# PWMDriver.net
KiCad netlist of a schematic drawn in Altium Designer
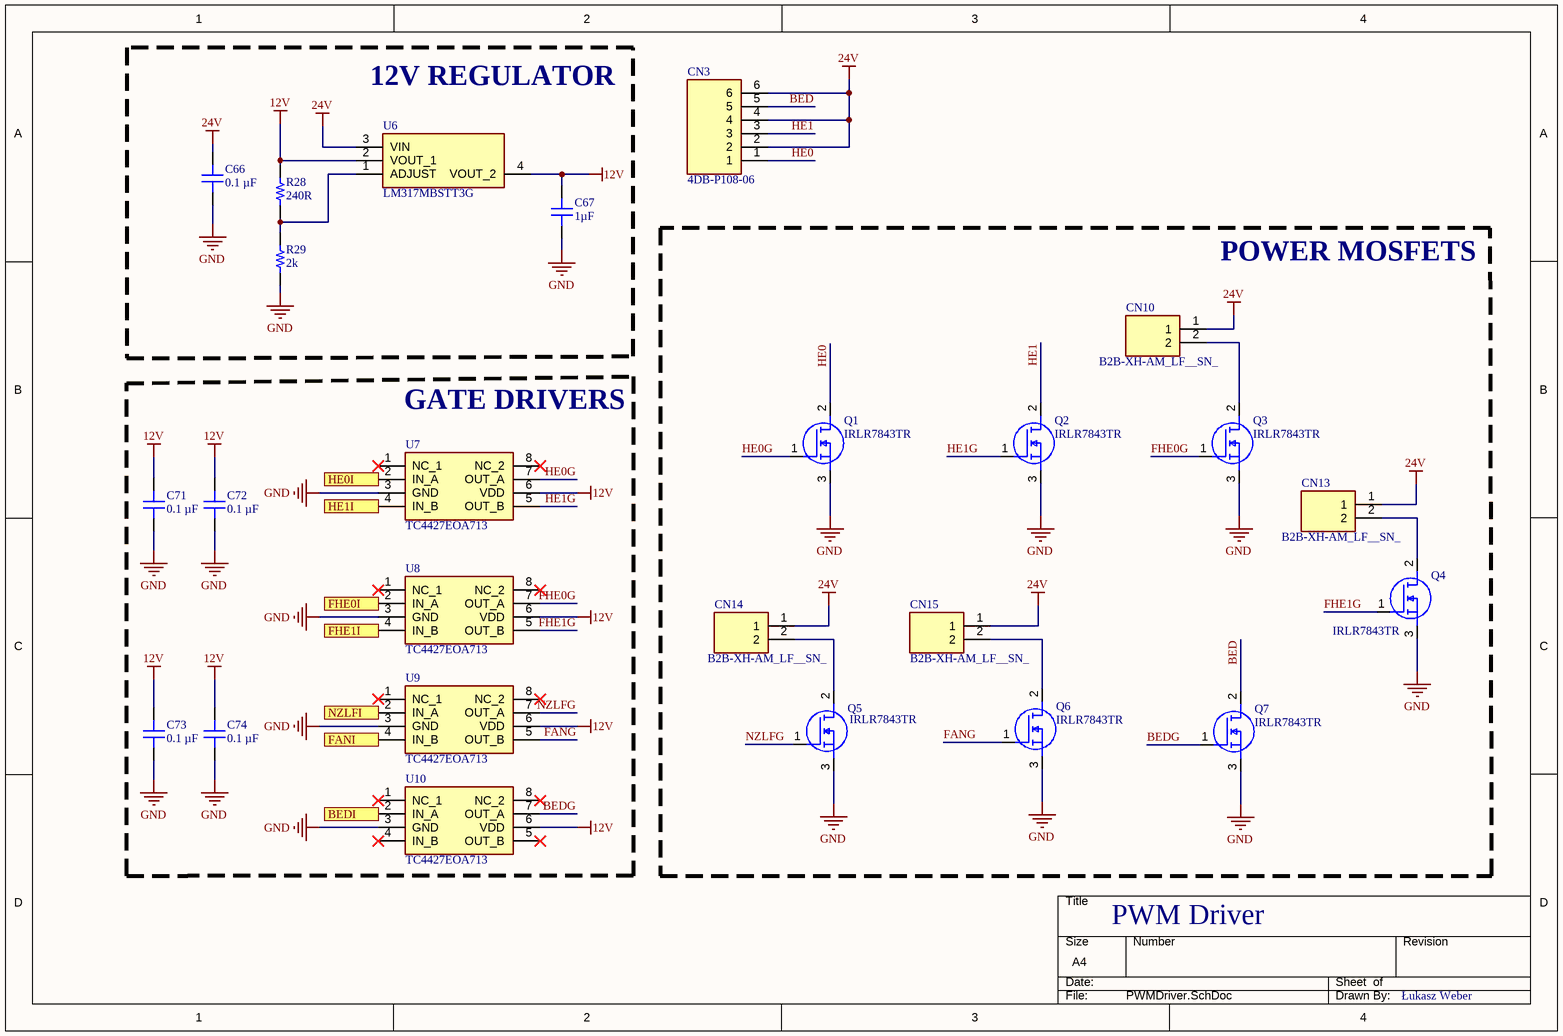
[diagram p0: PWMDriver.SchDoc]

(export (version "E")
  (design (tool "Eeschema 10.0.6"))
  (components
    (comp (ref "C66")
      (value "0.1 µF")
      (footprint "CAP 0603_1608")
      (description "CAP CER 0.1UF 100V X7R 0603")
      (fields
        (field (name "PART NUMBER") "0603B104K101CT")
        (field (name "MANUFACTURER") "Walsin Technology Corporation")
      )
      (libsource (lib "Celestial Altium Library - altium_library") (part "Capacitor"))
    )
    (comp (ref "C67")
      (value "1µF")
      (footprint "CAP 0603_1608")
      (description "CAP CER 1UF 16V X5R 0603")
      (fields (field (name "PART NUMBER") "0603YD105KAT4A") (field (name "MANUFACTURER") "AVX Corporation"))
      (libsource (lib "Celestial Altium Library - altium_library") (part "Capacitor"))
    )
    (comp (ref "C71")
      (value "0.1 µF")
      (footprint "CAP 0603_1608")
      (description "CAP CER 0.1UF 100V X7R 0603")
      (fields
        (field (name "PART NUMBER") "0603B104K101CT")
        (field (name "MANUFACTURER") "Walsin Technology Corporation")
      )
      (libsource (lib "Celestial Altium Library - altium_library") (part "Capacitor"))
    )
    (comp (ref "C72")
      (value "0.1 µF")
      (footprint "CAP 0603_1608")
      (description "CAP CER 0.1UF 100V X7R 0603")
      (fields
        (field (name "PART NUMBER") "0603B104K101CT")
        (field (name "MANUFACTURER") "Walsin Technology Corporation")
      )
      (libsource (lib "Celestial Altium Library - altium_library") (part "Capacitor"))
    )
    (comp (ref "C73")
      (value "0.1 µF")
      (footprint "CAP 0603_1608")
      (description "CAP CER 0.1UF 100V X7R 0603")
      (fields
        (field (name "PART NUMBER") "0603B104K101CT")
        (field (name "MANUFACTURER") "Walsin Technology Corporation")
      )
      (libsource (lib "Celestial Altium Library - altium_library") (part "Capacitor"))
    )
    (comp (ref "C74")
      (value "0.1 µF")
      (footprint "CAP 0603_1608")
      (description "CAP CER 0.1UF 100V X7R 0603")
      (fields
        (field (name "PART NUMBER") "0603B104K101CT")
        (field (name "MANUFACTURER") "Walsin Technology Corporation")
      )
      (libsource (lib "Celestial Altium Library - altium_library") (part "Capacitor"))
    )
    (comp (ref "CN3")
      (value "4DB-P108-06")
      (footprint "SamacSys:4DBP10806")
      (description "Connector")
      (fields (field (name "MOUSER PART NUMBER") "571-214376679"))
      (libsource (lib "*") (part "4DB-P108-06"))
    )
    (comp (ref "CN10")
      (value "B2B-XH-AM_LF__SN_")
      (footprint "Power Driver:B2BXHAMLFSN")
      (description "Connector")
      (fields (field (name "MANUFACTURER_PART_NUMBER") "B2B-XH-AM(LF)(SN)"))
      (libsource (lib "*") (part "B2B-XH-AM_LF__SN_"))
    )
    (comp (ref "CN13")
      (value "B2B-XH-AM_LF__SN_")
      (footprint "Power Driver:B2BXHAMLFSN")
      (description "Connector")
      (fields (field (name "MANUFACTURER_PART_NUMBER") "B2B-XH-AM(LF)(SN)"))
      (libsource (lib "*") (part "B2B-XH-AM_LF__SN_"))
    )
    (comp (ref "CN14")
      (value "B2B-XH-AM_LF__SN_")
      (footprint "Power Driver:B2BXHAMLFSN")
      (description "Connector")
      (fields (field (name "MANUFACTURER_PART_NUMBER") "B2B-XH-AM(LF)(SN)"))
      (libsource (lib "*") (part "B2B-XH-AM_LF__SN_"))
    )
    (comp (ref "CN15")
      (value "B2B-XH-AM_LF__SN_")
      (footprint "Power Driver:B2BXHAMLFSN")
      (description "Connector")
      (fields (field (name "MANUFACTURER_PART_NUMBER") "B2B-XH-AM(LF)(SN)"))
      (libsource (lib "*") (part "B2B-XH-AM_LF__SN_"))
    )
    (comp (ref "Q1")
      (value "IRLR7843TR")
      (footprint "SamacSys:IRLR7843TR")
      (description "MOSFET (N-Channel)")
      (libsource (lib "SamacSys") (part "IRLR7843TR"))
    )
    (comp (ref "Q2")
      (value "IRLR7843TR")
      (footprint "SamacSys:IRLR7843TR")
      (description "MOSFET (N-Channel)")
      (libsource (lib "SamacSys") (part "IRLR7843TR"))
    )
    (comp (ref "Q3")
      (value "IRLR7843TR")
      (footprint "SamacSys:IRLR7843TR")
      (description "MOSFET (N-Channel)")
      (libsource (lib "SamacSys") (part "IRLR7843TR"))
    )
    (comp (ref "Q4")
      (value "IRLR7843TR")
      (footprint "SamacSys:IRLR7843TR")
      (description "MOSFET (N-Channel)")
      (libsource (lib "SamacSys") (part "IRLR7843TR"))
    )
    (comp (ref "Q5")
      (value "IRLR7843TR")
      (footprint "SamacSys:IRLR7843TR")
      (description "MOSFET (N-Channel)")
      (libsource (lib "SamacSys") (part "IRLR7843TR"))
    )
    (comp (ref "Q6")
      (value "IRLR7843TR")
      (footprint "SamacSys:IRLR7843TR")
      (description "MOSFET (N-Channel)")
      (libsource (lib "SamacSys") (part "IRLR7843TR"))
    )
    (comp (ref "Q7")
      (value "IRLR7843TR")
      (footprint "SamacSys:IRLR7843TR")
      (description "MOSFET (N-Channel)")
      (libsource (lib "SamacSys") (part "IRLR7843TR"))
    )
    (comp (ref "R28")
      (value "240R")
      (footprint "RES 0603_1608")
      (description "RES SMD 240 OHM 1% 1/4W 0603")
      (fields (field (name "PART NUMBER") "RCS0603240RFKEA") (field (name "MANUFACTURER") "Vishay Dale"))
      (libsource (lib "Celestial Altium Library - altium_library") (part "Resistor"))
    )
    (comp (ref "R29")
      (value "2k")
      (footprint "RES 0603_1608")
      (description "RES SMD 2K OHM 5% 1/4W 0603")
      (fields (field (name "PART NUMBER") "ESR03EZPJ202") (field (name "MANUFACTURER") "Rohm Semiconductor"))
      (libsource (lib "Celestial Altium Library - altium_library") (part "Resistor"))
    )
    (comp (ref "U6")
      (value "LM317MBSTT3G")
      (footprint "Power Driver:SOT230P700X175-4N")
      (description "Integrated Circuit")
      (fields (field (name "MOUSER PART NUMBER") "863-LM317MBSTT3G"))
      (libsource (lib "*") (part "LM317MBSTT3G"))
    )
    (comp (ref "U7")
      (value "TC4427EOA713")
      (footprint "SamacSys:SOIC127P600X175-8N")
      (description "Integrated Circuit")
      (fields (field (name "MOUSER PART NUMBER") "579-TC4427EOA713"))
      (libsource (lib "*") (part "TC4427EOA713"))
    )
    (comp (ref "U8")
      (value "TC4427EOA713")
      (footprint "SamacSys:SOIC127P600X175-8N")
      (description "Integrated Circuit")
      (fields (field (name "MOUSER PART NUMBER") "579-TC4427EOA713"))
      (libsource (lib "*") (part "TC4427EOA713"))
    )
    (comp (ref "U9")
      (value "TC4427EOA713")
      (footprint "SamacSys:SOIC127P600X175-8N")
      (description "Integrated Circuit")
      (fields (field (name "MOUSER PART NUMBER") "579-TC4427EOA713"))
      (libsource (lib "*") (part "TC4427EOA713"))
    )
    (comp (ref "U10")
      (value "TC4427EOA713")
      (footprint "SamacSys:SOIC127P600X175-8N")
      (description "Integrated Circuit")
      (fields (field (name "MOUSER PART NUMBER") "579-TC4427EOA713"))
      (libsource (lib "*") (part "TC4427EOA713"))
    )
  )
  (nets
    (net (code "1") (name "/BED") (class "Default")
      (node (ref "CN3") (pin "5") (pinfunction "5_5") (pintype "passive"))
      (node (ref "Q7") (pin "2") (pinfunction "D_2") (pintype "passive"))
    )
    (net (code "2") (name "/BEDG") (class "Default")
      (node (ref "Q7") (pin "1") (pinfunction "G_1") (pintype "passive"))
      (node (ref "U10") (pin "7") (pinfunction "OUT_A_7") (pintype "passive"))
    )
    (net (code "3") (name "/BEDI") (class "Default")
      (node (ref "U10") (pin "2") (pinfunction "IN_A_2") (pintype "passive"))
    )
    (net (code "4") (name "/FANG") (class "Default")
      (node (ref "Q6") (pin "1") (pinfunction "G_1") (pintype "passive"))
      (node (ref "U9") (pin "5") (pinfunction "OUT_B_5") (pintype "passive"))
    )
    (net (code "5") (name "/FANI") (class "Default")
      (node (ref "U9") (pin "4") (pinfunction "IN_B_4") (pintype "passive"))
    )
    (net (code "6") (name "/FHE0G") (class "Default")
      (node (ref "Q3") (pin "1") (pinfunction "G_1") (pintype "passive"))
      (node (ref "U8") (pin "7") (pinfunction "OUT_A_7") (pintype "passive"))
    )
    (net (code "7") (name "/FHE0I") (class "Default")
      (node (ref "U8") (pin "2") (pinfunction "IN_A_2") (pintype "passive"))
    )
    (net (code "8") (name "/FHE1G") (class "Default")
      (node (ref "Q4") (pin "1") (pinfunction "G_1") (pintype "passive"))
      (node (ref "U8") (pin "5") (pinfunction "OUT_B_5") (pintype "passive"))
    )
    (net (code "9") (name "/FHE1I") (class "Default")
      (node (ref "U8") (pin "4") (pinfunction "IN_B_4") (pintype "passive"))
    )
    (net (code "10") (name "/HE0") (class "Default")
      (node (ref "CN3") (pin "1") (pinfunction "1_1") (pintype "passive"))
      (node (ref "Q1") (pin "2") (pinfunction "D_2") (pintype "passive"))
    )
    (net (code "11") (name "/HE0G") (class "Default")
      (node (ref "Q1") (pin "1") (pinfunction "G_1") (pintype "passive"))
      (node (ref "U7") (pin "7") (pinfunction "OUT_A_7") (pintype "passive"))
    )
    (net (code "12") (name "/HE0I") (class "Default")
      (node (ref "U7") (pin "2") (pinfunction "IN_A_2") (pintype "passive"))
    )
    (net (code "13") (name "/HE1") (class "Default")
      (node (ref "CN3") (pin "3") (pinfunction "3_3") (pintype "passive"))
      (node (ref "Q2") (pin "2") (pinfunction "D_2") (pintype "passive"))
    )
    (net (code "14") (name "/HE1G") (class "Default")
      (node (ref "Q2") (pin "1") (pinfunction "G_1") (pintype "passive"))
      (node (ref "U7") (pin "5") (pinfunction "OUT_B_5") (pintype "passive"))
    )
    (net (code "15") (name "/HE1I") (class "Default")
      (node (ref "U7") (pin "4") (pinfunction "IN_B_4") (pintype "passive"))
    )
    (net (code "16") (name "/NZLFG") (class "Default")
      (node (ref "Q5") (pin "1") (pinfunction "G_1") (pintype "passive"))
      (node (ref "U9") (pin "7") (pinfunction "OUT_A_7") (pintype "passive"))
    )
    (net (code "17") (name "/NZLFI") (class "Default")
      (node (ref "U9") (pin "2") (pinfunction "IN_A_2") (pintype "passive"))
    )
    (net (code "18") (name "12V") (class "Default")
      (node (ref "C67") (pin "2") (pinfunction "2_2") (pintype "passive"))
      (node (ref "C71") (pin "2") (pinfunction "2_2") (pintype "passive"))
      (node (ref "C72") (pin "2") (pinfunction "2_2") (pintype "passive"))
      (node (ref "C73") (pin "2") (pinfunction "2_2") (pintype "passive"))
      (node (ref "C74") (pin "2") (pinfunction "2_2") (pintype "passive"))
      (node (ref "R28") (pin "2") (pinfunction "2_2") (pintype "passive"))
      (node (ref "U10") (pin "6") (pinfunction "VDD_6") (pintype "passive"))
      (node (ref "U6") (pin "2") (pinfunction "VOUT_1_2") (pintype "passive"))
      (node (ref "U6") (pin "4") (pinfunction "VOUT_2_4") (pintype "passive"))
      (node (ref "U7") (pin "6") (pinfunction "VDD_6") (pintype "passive"))
      (node (ref "U8") (pin "6") (pinfunction "VDD_6") (pintype "passive"))
      (node (ref "U9") (pin "6") (pinfunction "VDD_6") (pintype "passive"))
    )
    (net (code "19") (name "24V") (class "Default")
      (node (ref "C66") (pin "2") (pinfunction "2_2") (pintype "passive"))
      (node (ref "CN10") (pin "1") (pinfunction "1_1") (pintype "passive"))
      (node (ref "CN13") (pin "1") (pinfunction "1_1") (pintype "passive"))
      (node (ref "CN14") (pin "1") (pinfunction "1_1") (pintype "passive"))
      (node (ref "CN15") (pin "1") (pinfunction "1_1") (pintype "passive"))
      (node (ref "CN3") (pin "2") (pinfunction "2_2") (pintype "passive"))
      (node (ref "CN3") (pin "4") (pinfunction "4_4") (pintype "passive"))
      (node (ref "CN3") (pin "6") (pinfunction "6_6") (pintype "passive"))
      (node (ref "U6") (pin "3") (pinfunction "VIN_3") (pintype "passive"))
    )
    (net (code "20") (name "GND") (class "Default")
      (node (ref "C66") (pin "1") (pinfunction "1_1") (pintype "passive"))
      (node (ref "C67") (pin "1") (pinfunction "1_1") (pintype "passive"))
      (node (ref "C71") (pin "1") (pinfunction "1_1") (pintype "passive"))
      (node (ref "C72") (pin "1") (pinfunction "1_1") (pintype "passive"))
      (node (ref "C73") (pin "1") (pinfunction "1_1") (pintype "passive"))
      (node (ref "C74") (pin "1") (pinfunction "1_1") (pintype "passive"))
      (node (ref "Q1") (pin "3") (pinfunction "S_3") (pintype "passive"))
      (node (ref "Q2") (pin "3") (pinfunction "S_3") (pintype "passive"))
      (node (ref "Q3") (pin "3") (pinfunction "S_3") (pintype "passive"))
      (node (ref "Q4") (pin "3") (pinfunction "S_3") (pintype "passive"))
      (node (ref "Q5") (pin "3") (pinfunction "S_3") (pintype "passive"))
      (node (ref "Q6") (pin "3") (pinfunction "S_3") (pintype "passive"))
      (node (ref "Q7") (pin "3") (pinfunction "S_3") (pintype "passive"))
      (node (ref "R29") (pin "1") (pinfunction "1_1") (pintype "passive"))
      (node (ref "U10") (pin "3") (pinfunction "GND_3") (pintype "passive"))
      (node (ref "U7") (pin "3") (pinfunction "GND_3") (pintype "passive"))
      (node (ref "U8") (pin "3") (pinfunction "GND_3") (pintype "passive"))
      (node (ref "U9") (pin "3") (pinfunction "GND_3") (pintype "passive"))
    )
    (net (code "21") (name "Net-(Q3-D)") (class "Default")
      (node (ref "CN10") (pin "2") (pinfunction "2_2") (pintype "passive"))
      (node (ref "Q3") (pin "2") (pinfunction "D_2") (pintype "passive"))
    )
    (net (code "22") (name "Net-(Q4-D)") (class "Default")
      (node (ref "CN13") (pin "2") (pinfunction "2_2") (pintype "passive"))
      (node (ref "Q4") (pin "2") (pinfunction "D_2") (pintype "passive"))
    )
    (net (code "23") (name "Net-(Q5-D)") (class "Default")
      (node (ref "CN14") (pin "2") (pinfunction "2_2") (pintype "passive"))
      (node (ref "Q5") (pin "2") (pinfunction "D_2") (pintype "passive"))
    )
    (net (code "24") (name "Net-(Q6-D)") (class "Default")
      (node (ref "CN15") (pin "2") (pinfunction "2_2") (pintype "passive"))
      (node (ref "Q6") (pin "2") (pinfunction "D_2") (pintype "passive"))
    )
    (net (code "25") (name "Net-(U6-ADJUST)") (class "Default")
      (node (ref "R28") (pin "1") (pinfunction "1_1") (pintype "passive"))
      (node (ref "R29") (pin "2") (pinfunction "2_2") (pintype "passive"))
      (node (ref "U6") (pin "1") (pinfunction "ADJUST_1") (pintype "passive"))
    )
    (net (code "26") (name "unconnected-(U7-NC_1-Pad1)") (class "Default")
      (node (ref "U7") (pin "1") (pinfunction "NC_1_1") (pintype "passive+no_connect"))
    )
    (net (code "27") (name "unconnected-(U7-NC_2-Pad8)") (class "Default")
      (node (ref "U7") (pin "8") (pinfunction "NC_2_8") (pintype "passive+no_connect"))
    )
    (net (code "28") (name "unconnected-(U8-NC_1-Pad1)") (class "Default")
      (node (ref "U8") (pin "1") (pinfunction "NC_1_1") (pintype "passive+no_connect"))
    )
    (net (code "29") (name "unconnected-(U8-NC_2-Pad8)") (class "Default")
      (node (ref "U8") (pin "8") (pinfunction "NC_2_8") (pintype "passive+no_connect"))
    )
    (net (code "30") (name "unconnected-(U9-NC_1-Pad1)") (class "Default")
      (node (ref "U9") (pin "1") (pinfunction "NC_1_1") (pintype "passive+no_connect"))
    )
    (net (code "31") (name "unconnected-(U9-NC_2-Pad8)") (class "Default")
      (node (ref "U9") (pin "8") (pinfunction "NC_2_8") (pintype "passive+no_connect"))
    )
    (net (code "32") (name "unconnected-(U10-IN_B-Pad4)") (class "Default")
      (node (ref "U10") (pin "4") (pinfunction "IN_B_4") (pintype "passive+no_connect"))
    )
    (net (code "33") (name "unconnected-(U10-NC_1-Pad1)") (class "Default")
      (node (ref "U10") (pin "1") (pinfunction "NC_1_1") (pintype "passive+no_connect"))
    )
    (net (code "34") (name "unconnected-(U10-NC_2-Pad8)") (class "Default")
      (node (ref "U10") (pin "8") (pinfunction "NC_2_8") (pintype "passive+no_connect"))
    )
    (net (code "35") (name "unconnected-(U10-OUT_B-Pad5)") (class "Default")
      (node (ref "U10") (pin "5") (pinfunction "OUT_B_5") (pintype "passive+no_connect"))
    )
  )
)
